# Bio_v4_LCD1_1.net
KiCad netlist of a schematic drawn in EAGLE
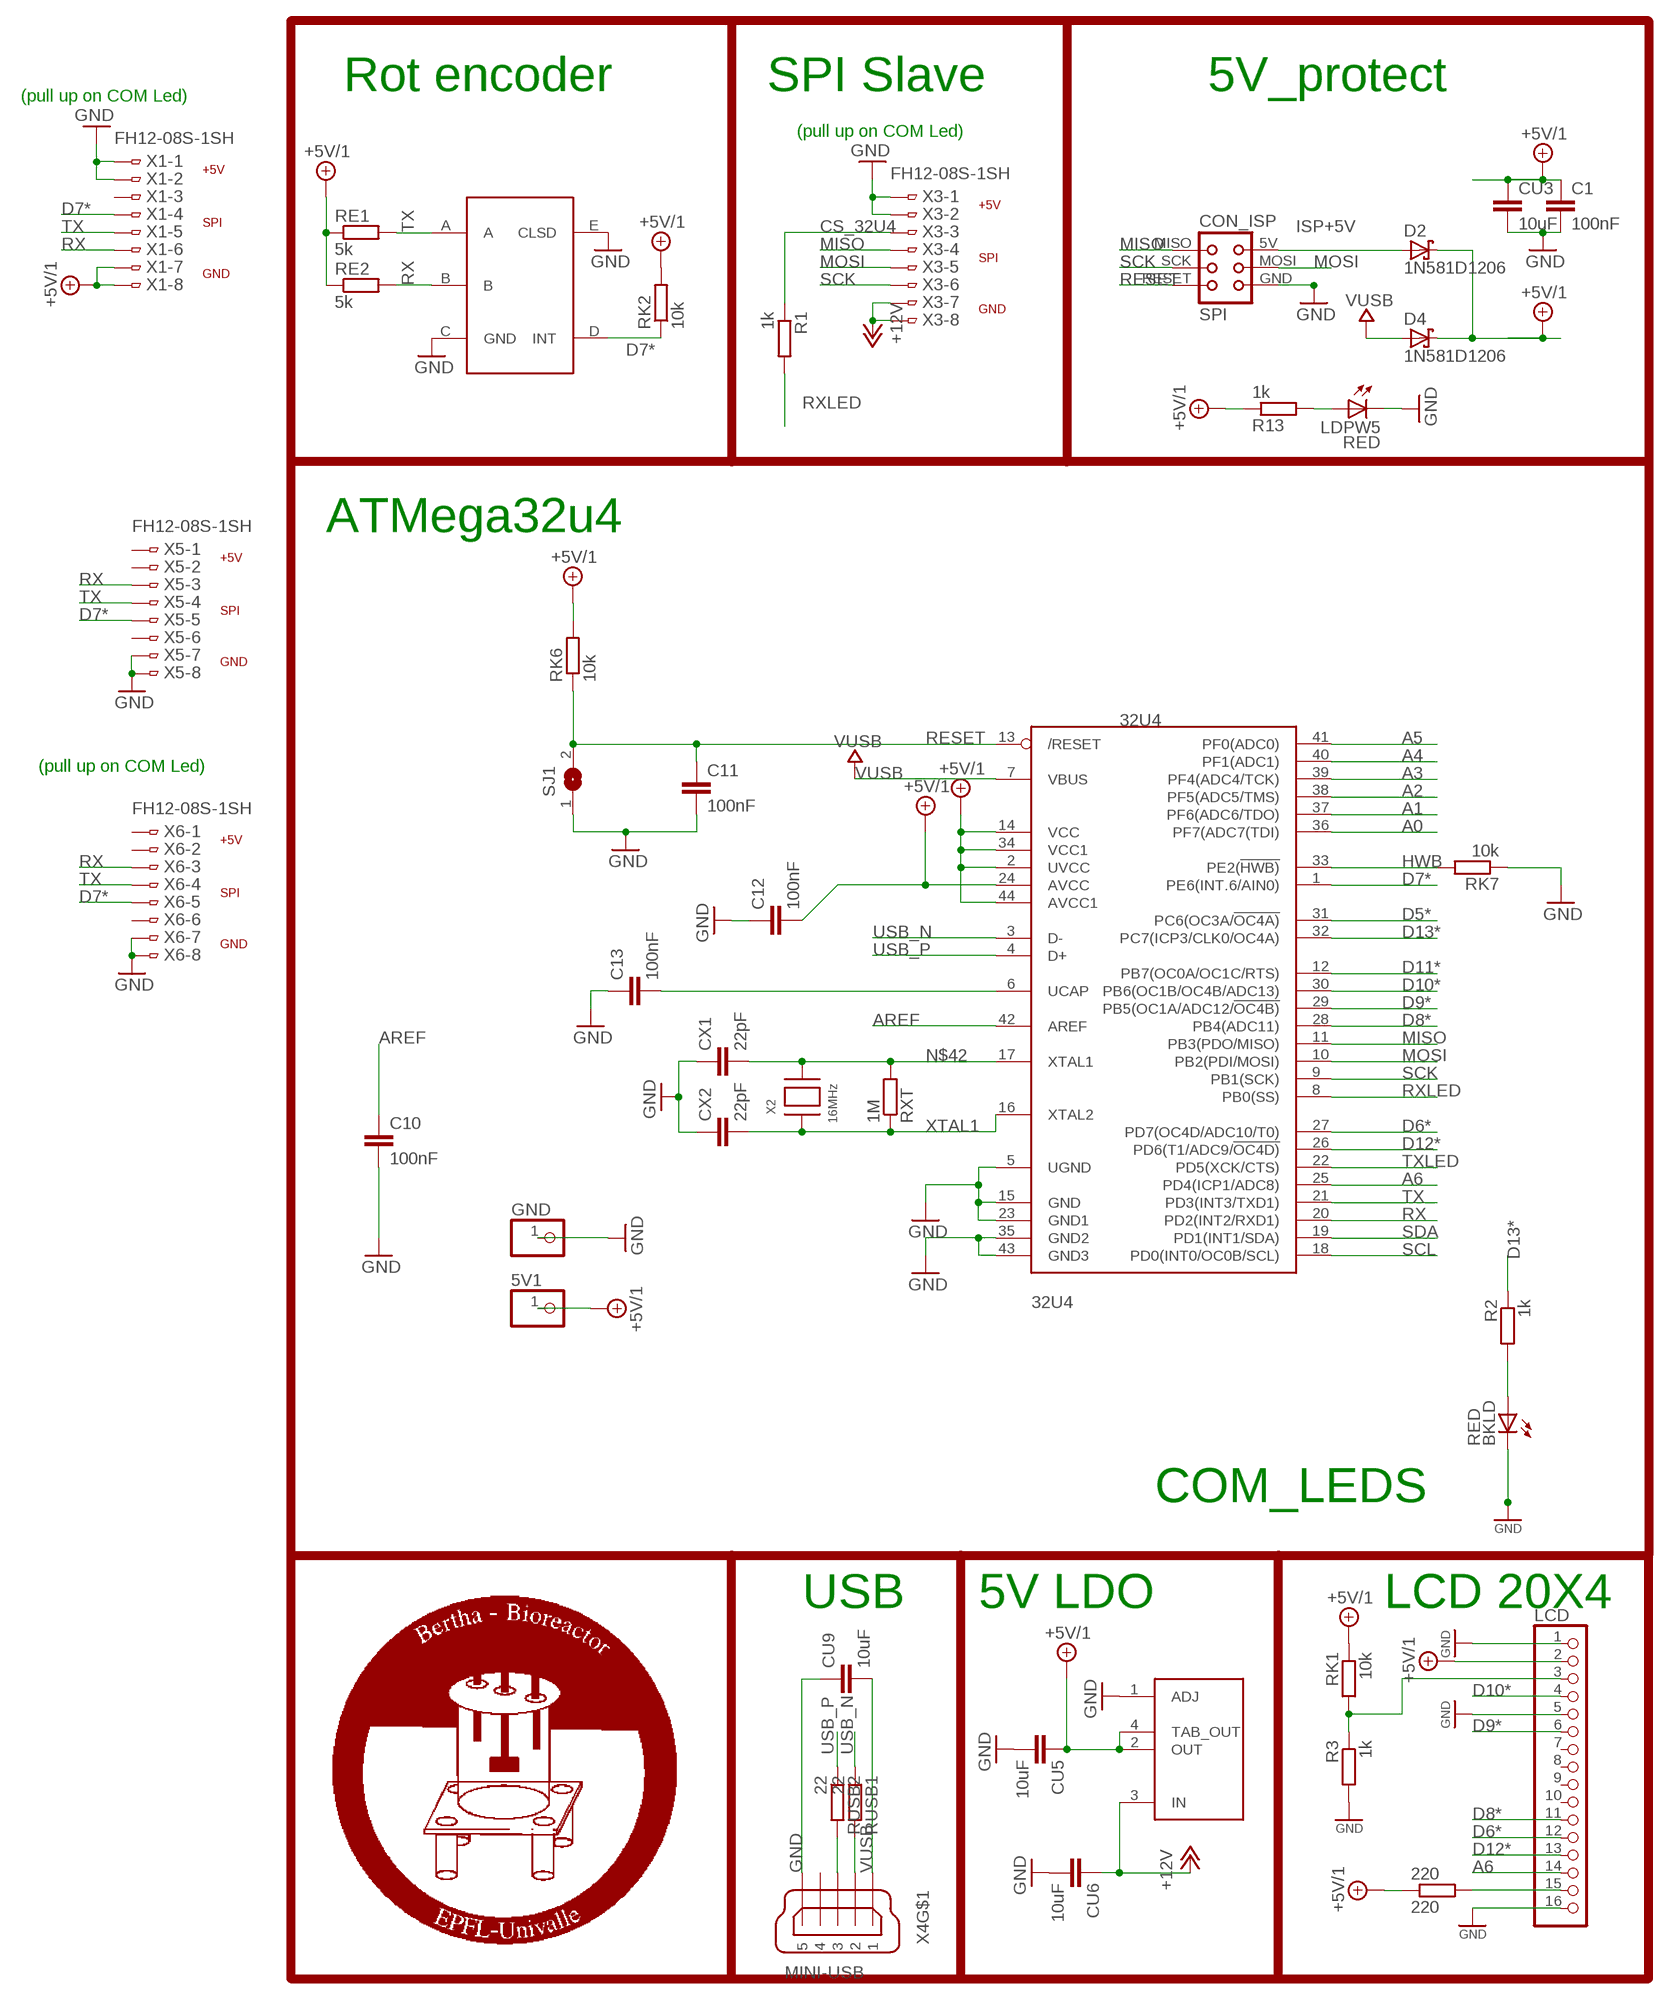
[diagram p0: schematic, sheet 1]

(export (version "E")
  (design (tool "Eeschema 10.0.6"))
  (components
    (comp (ref "5V1")
      (value "PINHD-1X1")
      (footprint "eagle-import:1X01")
      (libsource (lib "eagle-import") (part "PINHD-1X1"))
    )
    (comp (ref "32U4")
      (value "32U4")
      (footprint "eagle-import:TQFP44")
      (libsource (lib "eagle-import") (part "ATMEGA32U4-AU"))
    )
    (comp (ref "220")
      (value "220")
      (footprint "eagle-import:R0805")
      (libsource (lib "eagle-import") (part "R-EU_R0805"))
    )
    (comp (ref "BKLD")
      (value "RED")
      (footprint "eagle-import:CHIP-LED0805")
      (libsource (lib "eagle-import") (part "LEDCHIP-LED0805"))
    )
    (comp (ref "C1")
      (value "100nF")
      (footprint "eagle-import:C1206")
      (libsource (lib "eagle-import") (part "C-EUC1206"))
    )
    (comp (ref "C10")
      (value "100nF")
      (footprint "eagle-import:C1206")
      (libsource (lib "eagle-import") (part "C-EUC1206"))
    )
    (comp (ref "C11")
      (value "100nF")
      (footprint "eagle-import:C1206")
      (libsource (lib "eagle-import") (part "C-EUC1206"))
    )
    (comp (ref "C12")
      (value "100nF")
      (footprint "eagle-import:C1206")
      (libsource (lib "eagle-import") (part "C-EUC1206"))
    )
    (comp (ref "C13")
      (value "100nF")
      (footprint "eagle-import:C1206")
      (libsource (lib "eagle-import") (part "C-EUC1206"))
    )
    (comp (ref "CON_ISP")
      (value "SPI")
      (footprint "eagle-import:TC2030-MCP-NL")
      (libsource (lib "eagle-import") (part "TINYISPT"))
    )
    (comp (ref "CU3")
      (value "10uF")
      (footprint "eagle-import:C1206")
      (libsource (lib "eagle-import") (part "C-EUC1206"))
    )
    (comp (ref "CU5")
      (value "10uF")
      (footprint "eagle-import:C1206")
      (libsource (lib "eagle-import") (part "C-EUC1206"))
    )
    (comp (ref "CU6")
      (value "10uF")
      (footprint "eagle-import:C1206")
      (libsource (lib "eagle-import") (part "C-EUC1206"))
    )
    (comp (ref "CU9")
      (value "10uF")
      (footprint "eagle-import:C1206")
      (libsource (lib "eagle-import") (part "C-EUC1206"))
    )
    (comp (ref "CX1")
      (value "22pF")
      (footprint "eagle-import:C1206")
      (libsource (lib "eagle-import") (part "C-EUC1206"))
    )
    (comp (ref "CX2")
      (value "22pF")
      (footprint "eagle-import:C1206")
      (libsource (lib "eagle-import") (part "C-EUC1206"))
    )
    (comp (ref "D2")
      (value "1N581D1206")
      (footprint "eagle-import:LED-1206")
      (libsource (lib "eagle-import") (part "1N581D1206"))
    )
    (comp (ref "D4")
      (value "1N581D1206")
      (footprint "eagle-import:LED-1206")
      (libsource (lib "eagle-import") (part "1N581D1206"))
    )
    (comp (ref "GND")
      (value "PINHD-1X1")
      (footprint "eagle-import:1X01")
      (libsource (lib "eagle-import") (part "PINHD-1X1"))
    )
    (comp (ref "LCD")
      (value "LCD-HEADER")
      (footprint "eagle-import:1X16")
      (libsource (lib "eagle-import") (part "LCD-HEADER"))
    )
    (comp (ref "LDO")
      (value "NCP1117LPST50T3G")
      (footprint "eagle-import:SOT223")
      (libsource (lib "eagle-import") (part "NCP1117LPST50T3G"))
    )
    (comp (ref "LDPW5")
      (value "RED")
      (footprint "eagle-import:CHIP-LED0805")
      (libsource (lib "eagle-import") (part "LEDCHIP-LED0805"))
    )
    (comp (ref "R1")
      (value "1k")
      (footprint "eagle-import:R0805")
      (libsource (lib "eagle-import") (part "R-EU_R0805"))
    )
    (comp (ref "R2")
      (value "1k")
      (footprint "eagle-import:R0805")
      (libsource (lib "eagle-import") (part "R-EU_R0805"))
    )
    (comp (ref "R3")
      (value "1k")
      (footprint "eagle-import:R0805")
      (libsource (lib "eagle-import") (part "R-EU_R0805"))
    )
    (comp (ref "R13")
      (value "1k")
      (footprint "eagle-import:R0805")
      (libsource (lib "eagle-import") (part "resistor_R-EU_R0805"))
    )
    (comp (ref "RE1")
      (value "5k")
      (footprint "eagle-import:R0805")
      (libsource (lib "eagle-import") (part "R-EU_R0805"))
    )
    (comp (ref "RE2")
      (value "5k")
      (footprint "eagle-import:R0805")
      (libsource (lib "eagle-import") (part "R-EU_R0805"))
    )
    (comp (ref "RK1")
      (value "10k")
      (footprint "eagle-import:R0805")
      (libsource (lib "eagle-import") (part "R-EU_R0805"))
    )
    (comp (ref "RK2")
      (value "10k")
      (footprint "eagle-import:M0805")
      (libsource (lib "eagle-import") (part "resistor_R-EU_M0805"))
    )
    (comp (ref "RK6")
      (value "10k")
      (footprint "eagle-import:M0805")
      (libsource (lib "eagle-import") (part "resistor_R-EU_M0805"))
    )
    (comp (ref "RK7")
      (value "10k")
      (footprint "eagle-import:M0805")
      (libsource (lib "eagle-import") (part "resistor_R-EU_M0805"))
    )
    (comp (ref "RUSB1")
      (value "22")
      (footprint "eagle-import:M1206")
      (libsource (lib "eagle-import") (part "resistor_R-EU_M1206"))
    )
    (comp (ref "RUSB2")
      (value "22")
      (footprint "eagle-import:M1206")
      (libsource (lib "eagle-import") (part "resistor_R-EU_M1206"))
    )
    (comp (ref "RXT")
      (value "1M")
      (footprint "eagle-import:R0805")
      (libsource (lib "eagle-import") (part "R-EU_R0805"))
    )
    (comp (ref "SJ1") (value "SJ") (footprint "eagle-import:SJ") (libsource (lib "eagle-import") (part "SJ")))
    (comp (ref "U$1")
      (value "EC11E")
      (footprint "eagle-import:EC11E")
      (libsource (lib "eagle-import") (part "EC11E"))
    )
    (comp (ref "X1")
      (value "FH12-08S-1SH")
      (footprint "eagle-import:FH12-08S-1SH")
      (libsource (lib "eagle-import") (part "FH12-08S-1SH"))
    )
    (comp (ref "X2")
      (value "16MHz")
      (footprint "eagle-import:NX6035")
      (libsource (lib "eagle-import") (part "XTALNX6035"))
    )
    (comp (ref "X3")
      (value "FH12-08S-1SH")
      (footprint "eagle-import:FH12-08S-1SH")
      (libsource (lib "eagle-import") (part "FH12-08S-1SH"))
    )
    (comp (ref "X4")
      (value "MINI-USB")
      (footprint "eagle-import:32005-201")
      (libsource (lib "eagle-import") (part "MINI-USB-SCHIELD-32005-201"))
    )
    (comp (ref "X5")
      (value "FH12-08S-1SH")
      (footprint "eagle-import:FH12-08S-1SH")
      (libsource (lib "eagle-import") (part "FH12-08S-1SH"))
    )
    (comp (ref "X6")
      (value "FH12-08S-1SH")
      (footprint "eagle-import:FH12-08S-1SH")
      (libsource (lib "eagle-import") (part "FH12-08S-1SH"))
    )
  )
  (nets
    (net (code "1") (name "+5V{slash}1") (class "Default")
      (node (ref "220") (pin "1") (pinfunction "1_1") (pintype "passive"))
      (node (ref "32U4") (pin "14") (pinfunction "VCC_14") (pintype "bidirectional"))
      (node (ref "32U4") (pin "2") (pinfunction "UVCC_2") (pintype "bidirectional"))
      (node (ref "32U4") (pin "24") (pinfunction "AVCC_24") (pintype "bidirectional"))
      (node (ref "32U4") (pin "34") (pinfunction "VCC1_34") (pintype "bidirectional"))
      (node (ref "32U4") (pin "44") (pinfunction "AVCC1_44") (pintype "bidirectional"))
      (node (ref "5V1") (pin "1") (pinfunction "1_1") (pintype "passive"))
      (node (ref "C1") (pin "1") (pinfunction "1_1") (pintype "passive"))
      (node (ref "C12") (pin "2") (pinfunction "2_2") (pintype "passive"))
      (node (ref "CU3") (pin "1") (pinfunction "1_1") (pintype "passive"))
      (node (ref "CU5") (pin "1") (pinfunction "1_1") (pintype "passive"))
      (node (ref "D2") (pin "C") (pinfunction "C_C") (pintype "passive"))
      (node (ref "D4") (pin "C") (pinfunction "C_C") (pintype "passive"))
      (node (ref "LCD") (pin "2") (pinfunction "2_2") (pintype "passive"))
      (node (ref "LDO") (pin "2") (pinfunction "OUT_2") (pintype "bidirectional"))
      (node (ref "LDO") (pin "4") (pinfunction "TAB_OUT_4") (pintype "bidirectional"))
      (node (ref "R13") (pin "1") (pinfunction "1_1") (pintype "passive"))
      (node (ref "RE1") (pin "1") (pinfunction "1_1") (pintype "passive"))
      (node (ref "RE2") (pin "1") (pinfunction "1_1") (pintype "passive"))
      (node (ref "RK1") (pin "1") (pinfunction "1_1") (pintype "passive"))
      (node (ref "RK2") (pin "2") (pinfunction "2_2") (pintype "passive"))
      (node (ref "RK6") (pin "2") (pinfunction "2_2") (pintype "passive"))
      (node (ref "X1") (pin "7") (pinfunction "1_7") (pintype "passive"))
      (node (ref "X1") (pin "8") (pinfunction "1_8") (pintype "passive"))
    )
    (net (code "2") (name "+12V") (class "Default")
      (node (ref "CU6") (pin "1") (pinfunction "1_1") (pintype "passive"))
      (node (ref "LDO") (pin "3") (pinfunction "IN_3") (pintype "bidirectional"))
      (node (ref "X3") (pin "7") (pinfunction "1_7") (pintype "passive"))
      (node (ref "X3") (pin "8") (pinfunction "1_8") (pintype "passive"))
    )
    (net (code "3") (name "/A0") (class "Default")
      (node (ref "32U4") (pin "36") (pinfunction "PF7(ADC7(TDI)_36") (pintype "bidirectional"))
    )
    (net (code "4") (name "/A1") (class "Default")
      (node (ref "32U4") (pin "37") (pinfunction "PF6(ADC6/TDO)_37") (pintype "bidirectional"))
    )
    (net (code "5") (name "/A2") (class "Default")
      (node (ref "32U4") (pin "38") (pinfunction "PF5(ADC5/TMS)_38") (pintype "bidirectional"))
    )
    (net (code "6") (name "/A3") (class "Default")
      (node (ref "32U4") (pin "39") (pinfunction "PF4(ADC4/TCK)_39") (pintype "bidirectional"))
    )
    (net (code "7") (name "/A4") (class "Default")
      (node (ref "32U4") (pin "40") (pinfunction "PF1(ADC1)_40") (pintype "bidirectional"))
    )
    (net (code "8") (name "/A5") (class "Default")
      (node (ref "32U4") (pin "41") (pinfunction "PF0(ADC0)_41") (pintype "bidirectional"))
    )
    (net (code "9") (name "/A6") (class "Default")
      (node (ref "32U4") (pin "25") (pinfunction "PD4(ICP1/ADC8)_25") (pintype "bidirectional"))
      (node (ref "LCD") (pin "14") (pinfunction "14_14") (pintype "passive"))
    )
    (net (code "10") (name "/AREF") (class "Default")
      (node (ref "32U4") (pin "42") (pinfunction "AREF_42") (pintype "bidirectional"))
      (node (ref "C10") (pin "1") (pinfunction "1_1") (pintype "passive"))
    )
    (net (code "11") (name "/CS_32U4") (class "Default")
      (node (ref "R1") (pin "1") (pinfunction "1_1") (pintype "passive"))
      (node (ref "X3") (pin "3") (pinfunction "1_3") (pintype "passive"))
    )
    (net (code "12") (name "/D5*") (class "Default")
      (node (ref "32U4") (pin "31") (pinfunction "PC6(OC3A/~{OC4A})_31") (pintype "bidirectional"))
    )
    (net (code "13") (name "/D6*") (class "Default")
      (node (ref "32U4") (pin "27") (pinfunction "PD7(OC4D/ADC10/T0)_27") (pintype "bidirectional"))
      (node (ref "LCD") (pin "12") (pinfunction "12_12") (pintype "passive"))
    )
    (net (code "14") (name "/D7*") (class "Default")
      (node (ref "32U4") (pin "1") (pinfunction "PE6(INT.6/AIN0)_1") (pintype "bidirectional"))
      (node (ref "RK2") (pin "1") (pinfunction "1_1") (pintype "passive"))
      (node (ref "U$1") (pin "D") (pinfunction "INT_D") (pintype "bidirectional"))
      (node (ref "X1") (pin "4") (pinfunction "1_4") (pintype "passive"))
      (node (ref "X5") (pin "5") (pinfunction "1_5") (pintype "passive"))
      (node (ref "X6") (pin "5") (pinfunction "1_5") (pintype "passive"))
    )
    (net (code "15") (name "/D8*") (class "Default")
      (node (ref "32U4") (pin "28") (pinfunction "PB4(ADC11)_28") (pintype "bidirectional"))
      (node (ref "LCD") (pin "11") (pinfunction "11_11") (pintype "passive"))
    )
    (net (code "16") (name "/D9*") (class "Default")
      (node (ref "32U4") (pin "29") (pinfunction "PB5(OC1A/ADC12/~{OC4B})_29") (pintype "bidirectional"))
      (node (ref "LCD") (pin "6") (pinfunction "6_6") (pintype "passive"))
    )
    (net (code "17") (name "/D10*") (class "Default")
      (node (ref "32U4") (pin "30") (pinfunction "PB6(OC1B/OC4B/ADC13)_30") (pintype "bidirectional"))
      (node (ref "LCD") (pin "4") (pinfunction "4_4") (pintype "passive"))
    )
    (net (code "18") (name "/D11*") (class "Default")
      (node (ref "32U4") (pin "12") (pinfunction "PB7(OC0A/OC1C/RTS)_12") (pintype "bidirectional"))
    )
    (net (code "19") (name "/D12*") (class "Default")
      (node (ref "32U4") (pin "26") (pinfunction "PD6(T1/ADC9/~{OC4D})_26") (pintype "bidirectional"))
      (node (ref "LCD") (pin "13") (pinfunction "13_13") (pintype "passive"))
    )
    (net (code "20") (name "/D13*") (class "Default")
      (node (ref "32U4") (pin "32") (pinfunction "PC7(ICP3/CLK0/OC4A)_32") (pintype "bidirectional"))
      (node (ref "R2") (pin "1") (pinfunction "1_1") (pintype "passive"))
    )
    (net (code "21") (name "/HWB") (class "Default")
      (node (ref "32U4") (pin "33") (pinfunction "PE2(~{HWB})_33") (pintype "bidirectional"))
      (node (ref "RK7") (pin "2") (pinfunction "2_2") (pintype "passive"))
    )
    (net (code "22") (name "/ISP+5V") (class "Default")
      (node (ref "CON_ISP") (pin "5V") (pinfunction "VCC_5V") (pintype "passive"))
      (node (ref "D2") (pin "A") (pinfunction "A_A") (pintype "passive"))
    )
    (net (code "23") (name "/MISO") (class "Default")
      (node (ref "32U4") (pin "11") (pinfunction "PB3(PDO/MISO)_11") (pintype "bidirectional"))
      (node (ref "CON_ISP") (pin "MISO") (pinfunction "MISO_MISO") (pintype "passive"))
      (node (ref "X3") (pin "4") (pinfunction "1_4") (pintype "passive"))
    )
    (net (code "24") (name "/MOSI") (class "Default")
      (node (ref "32U4") (pin "10") (pinfunction "PB2(PDI/MOSI)_10") (pintype "bidirectional"))
      (node (ref "CON_ISP") (pin "MOSI") (pinfunction "MOSI_MOSI") (pintype "passive"))
      (node (ref "X3") (pin "5") (pinfunction "1_5") (pintype "passive"))
    )
    (net (code "25") (name "/N$42") (class "Default")
      (node (ref "32U4") (pin "17") (pinfunction "XTAL1_17") (pintype "bidirectional"))
      (node (ref "CX1") (pin "2") (pinfunction "2_2") (pintype "passive"))
      (node (ref "RXT") (pin "2") (pinfunction "2_2") (pintype "passive"))
      (node (ref "X2") (pin "P$2") (pinfunction "P$2_P$2") (pintype "bidirectional"))
    )
    (net (code "26") (name "/RESET") (class "Default")
      (node (ref "32U4") (pin "13") (pinfunction "/RESET_13") (pintype "bidirectional"))
      (node (ref "C11") (pin "1") (pinfunction "1_1") (pintype "passive"))
      (node (ref "CON_ISP") (pin "RESET") (pinfunction "RESET_RESET") (pintype "passive"))
      (node (ref "RK6") (pin "1") (pinfunction "1_1") (pintype "passive"))
      (node (ref "SJ1") (pin "2") (pinfunction "2_2") (pintype "passive"))
    )
    (net (code "27") (name "/RX") (class "Default")
      (node (ref "32U4") (pin "20") (pinfunction "PD2(INT2/RXD1)_20") (pintype "bidirectional"))
      (node (ref "RE2") (pin "2") (pinfunction "2_2") (pintype "passive"))
      (node (ref "U$1") (pin "B") (pinfunction "B_B") (pintype "bidirectional"))
      (node (ref "X1") (pin "6") (pinfunction "1_6") (pintype "passive"))
      (node (ref "X5") (pin "3") (pinfunction "1_3") (pintype "passive"))
      (node (ref "X6") (pin "3") (pinfunction "1_3") (pintype "passive"))
    )
    (net (code "28") (name "/RXLED") (class "Default")
      (node (ref "32U4") (pin "8") (pinfunction "PB0(SS)_8") (pintype "bidirectional"))
      (node (ref "R1") (pin "2") (pinfunction "2_2") (pintype "passive"))
    )
    (net (code "29") (name "/SCK") (class "Default")
      (node (ref "32U4") (pin "9") (pinfunction "PB1(SCK)_9") (pintype "bidirectional"))
      (node (ref "CON_ISP") (pin "SCK") (pinfunction "SCK_SCK") (pintype "passive"))
      (node (ref "X3") (pin "6") (pinfunction "1_6") (pintype "passive"))
    )
    (net (code "30") (name "/SCL") (class "Default")
      (node (ref "32U4") (pin "18") (pinfunction "PD0(INT0/OC0B/SCL)_18") (pintype "bidirectional"))
    )
    (net (code "31") (name "/SDA") (class "Default")
      (node (ref "32U4") (pin "19") (pinfunction "PD1(INT1/SDA)_19") (pintype "bidirectional"))
    )
    (net (code "32") (name "/TX") (class "Default")
      (node (ref "32U4") (pin "21") (pinfunction "PD3(INT3/TXD1)_21") (pintype "bidirectional"))
      (node (ref "RE1") (pin "2") (pinfunction "2_2") (pintype "passive"))
      (node (ref "U$1") (pin "A") (pinfunction "A_A") (pintype "bidirectional"))
      (node (ref "X1") (pin "5") (pinfunction "1_5") (pintype "passive"))
      (node (ref "X5") (pin "4") (pinfunction "1_4") (pintype "passive"))
      (node (ref "X6") (pin "4") (pinfunction "1_4") (pintype "passive"))
    )
    (net (code "33") (name "/TXLED") (class "Default")
      (node (ref "32U4") (pin "22") (pinfunction "PD5(XCK/CTS)_22") (pintype "bidirectional"))
    )
    (net (code "34") (name "/USB_N") (class "Default")
      (node (ref "32U4") (pin "3") (pinfunction "D-_3") (pintype "bidirectional"))
      (node (ref "RUSB1") (pin "1") (pinfunction "1_1") (pintype "passive"))
    )
    (net (code "35") (name "/USB_P") (class "Default")
      (node (ref "32U4") (pin "4") (pinfunction "D+_4") (pintype "bidirectional"))
      (node (ref "RUSB2") (pin "1") (pinfunction "1_1") (pintype "passive"))
    )
    (net (code "36") (name "/XTAL1") (class "Default")
      (node (ref "32U4") (pin "16") (pinfunction "XTAL2_16") (pintype "bidirectional"))
      (node (ref "CX2") (pin "2") (pinfunction "2_2") (pintype "passive"))
      (node (ref "RXT") (pin "1") (pinfunction "1_1") (pintype "passive"))
      (node (ref "X2") (pin "P$1") (pinfunction "P$1_P$1") (pintype "bidirectional"))
    )
    (net (code "37") (name "GND") (class "Default")
      (node (ref "32U4") (pin "15") (pinfunction "GND_15") (pintype "bidirectional"))
      (node (ref "32U4") (pin "23") (pinfunction "GND1_23") (pintype "bidirectional"))
      (node (ref "32U4") (pin "35") (pinfunction "GND2_35") (pintype "bidirectional"))
      (node (ref "32U4") (pin "43") (pinfunction "GND3_43") (pintype "bidirectional"))
      (node (ref "32U4") (pin "5") (pinfunction "UGND_5") (pintype "bidirectional"))
      (node (ref "BKLD") (pin "C") (pinfunction "C_C") (pintype "passive"))
      (node (ref "C1") (pin "2") (pinfunction "2_2") (pintype "passive"))
      (node (ref "C10") (pin "2") (pinfunction "2_2") (pintype "passive"))
      (node (ref "C11") (pin "2") (pinfunction "2_2") (pintype "passive"))
      (node (ref "C12") (pin "1") (pinfunction "1_1") (pintype "passive"))
      (node (ref "C13") (pin "1") (pinfunction "1_1") (pintype "passive"))
      (node (ref "CON_ISP") (pin "GND") (pinfunction "GND_GND") (pintype "passive"))
      (node (ref "CU3") (pin "2") (pinfunction "2_2") (pintype "passive"))
      (node (ref "CU5") (pin "2") (pinfunction "2_2") (pintype "passive"))
      (node (ref "CU6") (pin "2") (pinfunction "2_2") (pintype "passive"))
      (node (ref "CU9") (pin "1") (pinfunction "1_1") (pintype "passive"))
      (node (ref "CX1") (pin "1") (pinfunction "1_1") (pintype "passive"))
      (node (ref "CX2") (pin "1") (pinfunction "1_1") (pintype "passive"))
      (node (ref "GND") (pin "1") (pinfunction "1_1") (pintype "passive"))
      (node (ref "LCD") (pin "1") (pinfunction "1_1") (pintype "passive"))
      (node (ref "LCD") (pin "16") (pinfunction "16_16") (pintype "passive"))
      (node (ref "LCD") (pin "5") (pinfunction "5_5") (pintype "passive"))
      (node (ref "LDO") (pin "1") (pinfunction "ADJ_1") (pintype "bidirectional"))
      (node (ref "LDPW5") (pin "C") (pinfunction "C_C") (pintype "passive"))
      (node (ref "R3") (pin "2") (pinfunction "2_2") (pintype "passive"))
      (node (ref "RK7") (pin "1") (pinfunction "1_1") (pintype "passive"))
      (node (ref "SJ1") (pin "1") (pinfunction "1_1") (pintype "passive"))
      (node (ref "U$1") (pin "C") (pinfunction "GND_C") (pintype "bidirectional"))
      (node (ref "U$1") (pin "E") (pinfunction "CLSD_E") (pintype "bidirectional"))
      (node (ref "X1") (pin "1") (pinfunction "1_1") (pintype "passive"))
      (node (ref "X1") (pin "2") (pinfunction "1_2") (pintype "passive"))
      (node (ref "X3") (pin "1") (pinfunction "1_1") (pintype "passive"))
      (node (ref "X3") (pin "2") (pinfunction "1_2") (pintype "passive"))
      (node (ref "X4") (pin "5") (pinfunction "5_5") (pintype "passive"))
      (node (ref "X5") (pin "7") (pinfunction "1_7") (pintype "passive"))
      (node (ref "X5") (pin "8") (pinfunction "1_8") (pintype "passive"))
      (node (ref "X6") (pin "7") (pinfunction "1_7") (pintype "passive"))
      (node (ref "X6") (pin "8") (pinfunction "1_8") (pintype "passive"))
    )
    (net (code "38") (name "Net-(32U4-UCAP)") (class "Default")
      (node (ref "32U4") (pin "6") (pinfunction "UCAP_6") (pintype "bidirectional"))
      (node (ref "C13") (pin "2") (pinfunction "2_2") (pintype "passive"))
    )
    (net (code "39") (name "Net-(220-Pad2)") (class "Default")
      (node (ref "220") (pin "2") (pinfunction "2_2") (pintype "passive"))
      (node (ref "LCD") (pin "15") (pinfunction "15_15") (pintype "passive"))
    )
    (net (code "40") (name "Net-(BKLD-PadA)") (class "Default")
      (node (ref "BKLD") (pin "A") (pinfunction "A_A") (pintype "passive"))
      (node (ref "R2") (pin "2") (pinfunction "2_2") (pintype "passive"))
    )
    (net (code "41") (name "Net-(LCD-Pad3)") (class "Default")
      (node (ref "LCD") (pin "3") (pinfunction "3_3") (pintype "passive"))
      (node (ref "R3") (pin "1") (pinfunction "1_1") (pintype "passive"))
      (node (ref "RK1") (pin "2") (pinfunction "2_2") (pintype "passive"))
    )
    (net (code "42") (name "Net-(LDPW5-PadA)") (class "Default")
      (node (ref "LDPW5") (pin "A") (pinfunction "A_A") (pintype "passive"))
      (node (ref "R13") (pin "2") (pinfunction "2_2") (pintype "passive"))
    )
    (net (code "43") (name "Net-(RUSB1-Pad2)") (class "Default")
      (node (ref "RUSB1") (pin "2") (pinfunction "2_2") (pintype "passive"))
      (node (ref "X4") (pin "2") (pinfunction "2_2") (pintype "passive"))
    )
    (net (code "44") (name "Net-(RUSB2-Pad2)") (class "Default")
      (node (ref "RUSB2") (pin "2") (pinfunction "2_2") (pintype "passive"))
      (node (ref "X4") (pin "3") (pinfunction "3_3") (pintype "passive"))
    )
    (net (code "45") (name "VUSB") (class "Default")
      (node (ref "32U4") (pin "7") (pinfunction "VBUS_7") (pintype "bidirectional"))
      (node (ref "CU9") (pin "2") (pinfunction "2_2") (pintype "passive"))
      (node (ref "D4") (pin "A") (pinfunction "A_A") (pintype "passive"))
      (node (ref "X4") (pin "1") (pinfunction "1_1") (pintype "passive"))
    )
    (net (code "46") (name "unconnected-(LCD-Pad7)") (class "Default")
      (node (ref "LCD") (pin "7") (pinfunction "7_7") (pintype "passive"))
    )
    (net (code "47") (name "unconnected-(LCD-Pad8)") (class "Default")
      (node (ref "LCD") (pin "8") (pinfunction "8_8") (pintype "passive"))
    )
    (net (code "48") (name "unconnected-(LCD-Pad9)") (class "Default")
      (node (ref "LCD") (pin "9") (pinfunction "9_9") (pintype "passive"))
    )
    (net (code "49") (name "unconnected-(LCD-Pad10)") (class "Default")
      (node (ref "LCD") (pin "10") (pinfunction "10_10") (pintype "passive"))
    )
    (net (code "50") (name "unconnected-(X1C-1-Pad3)") (class "Default")
      (node (ref "X1") (pin "3") (pinfunction "1_3") (pintype "passive"))
    )
    (net (code "51") (name "unconnected-(X4-Pad4)") (class "Default")
      (node (ref "X4") (pin "4") (pinfunction "4_4") (pintype "passive"))
    )
    (net (code "52") (name "unconnected-(X5-Pad1)") (class "Default")
      (node (ref "X5") (pin "1") (pinfunction "1_1") (pintype "passive"))
    )
    (net (code "53") (name "unconnected-(X5B-1-Pad2)") (class "Default")
      (node (ref "X5") (pin "2") (pinfunction "1_2") (pintype "passive"))
    )
    (net (code "54") (name "unconnected-(X5F-1-Pad6)") (class "Default")
      (node (ref "X5") (pin "6") (pinfunction "1_6") (pintype "passive"))
    )
    (net (code "55") (name "unconnected-(X6-Pad1)") (class "Default")
      (node (ref "X6") (pin "1") (pinfunction "1_1") (pintype "passive"))
    )
    (net (code "56") (name "unconnected-(X6B-1-Pad2)") (class "Default")
      (node (ref "X6") (pin "2") (pinfunction "1_2") (pintype "passive"))
    )
    (net (code "57") (name "unconnected-(X6F-1-Pad6)") (class "Default")
      (node (ref "X6") (pin "6") (pinfunction "1_6") (pintype "passive"))
    )
  )
)
